# 03_-_VOLTAGE_REGULATION.net
KiCad netlist of a schematic drawn in Altium Designer
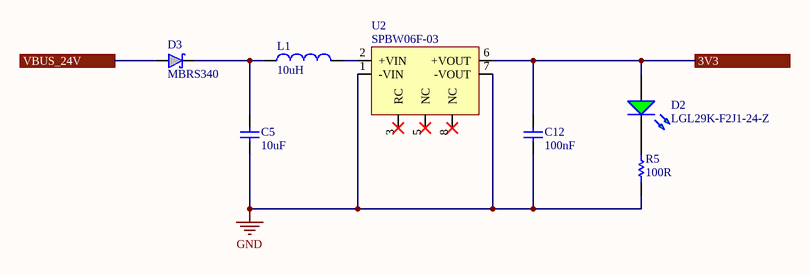
[diagram p0: [03] - VOLTAGE REGULATION.SchDoc]

(export (version "E")
  (design (tool "Eeschema 10.0.6"))
  (components
    (comp (ref "C5")
      (value "10uF")
      (footprint "INCH 1206 - METRIC 3216 - H180")
      (description "CAP CER 10UF 50V X5R 1206")
      (fields
        (field (name "MANUFACTURER") "TDK")
        (field (name "MANUFACTURER PART NUMBER") "C3216X5R1H106K160AB")
      )
      (libsource (lib "Capacitors") (part "C3216X5R1H106K160AB"))
    )
    (comp (ref "C12")
      (value "100nF")
      (footprint "INCH 0603 - METRIC 1608 - H090")
      (description "CAP CER 0.1UF 25V X7R 0603")
      (fields
        (field (name "MANUFACTURER") "TDK")
        (field (name "MANUFACTURER PART NUMBER") "CGA3E2X7R1E104K080AA")
      )
      (libsource (lib "Capacitors") (part "CGA3E2X7R1E104K080AA"))
    )
    (comp (ref "D2")
      (value "LGL29K-F2J1-24-Z")
      (footprint "LED - 0603 - GREEN")
      (description "LED GREEN DIFFUSED 0603 SMD")
      (fields (field (name "MANUFACTURER") "Osram Opto"))
      (libsource (lib "LEDs") (part "LGL29K-F2J1-24-Z"))
    )
    (comp (ref "D3")
      (value "MBRS340")
      (footprint "D0-214AB SMC - L")
      (description "DIODE SCHOTTKY 40V 4A SMC")
      (fields (field (name "MANUFACTURER") "ON Semiconductor / Fairchild"))
      (libsource (lib "Diodes") (part "MBRS340"))
    )
    (comp (ref "L1")
      (value "10uH")
      (footprint "VISHAY_IHLP2020BZER100M01")
      (description "FIXED IND 10UH 2.3A 199 MOHM SMD")
      (fields
        (field (name "MANUFACTURER") "Vishay Dale")
        (field (name "MANUFACTURER PART NUMBER") "IHLP2020BZER100M01")
      )
      (libsource (lib "Inductors") (part "IHLP2020BZER100M01"))
    )
    (comp (ref "R5")
      (value "100R")
      (footprint "INCH 0603 - METRIC 1608 - H055")
      (description "RES SMD 100 OHM 0.1% 1/16W 0603")
      (fields
        (field (name "MANUFACTURER") "TE Connectivity Neohm")
        (field (name "MANUFACTURER PART NUMBER") "CPF0603B100RE1")
      )
      (libsource (lib "Resistors") (part "CPF0603B100RE1"))
    )
    (comp (ref "U2")
      (value "SPBW06F-03")
      (footprint "SPBW06F-03")
      (description "DC DC CONVERTER 3.3V 5W")
      (fields (field (name "MANUFACTURER") "Mean Well"))
      (libsource (lib "Voltage Regulators - Switching") (part "SPBW06F-03"))
    )
  )
  (nets
    (net (code "1") (name "/3V3") (class "Default")
      (node (ref "C12") (pin "2") (pintype "passive"))
      (node (ref "D2") (pin "A") (pintype "passive"))
      (node (ref "U2") (pin "6") (pinfunction "+VOUT_6") (pintype "passive"))
    )
    (net (code "2") (name "/VBUS_24V") (class "Default") (node (ref "D3") (pin "2") (pintype "passive")))
    (net (code "3") (name "GND") (class "Default")
      (node (ref "C12") (pin "1") (pintype "passive"))
      (node (ref "C5") (pin "1") (pintype "passive"))
      (node (ref "R5") (pin "2") (pintype "passive"))
      (node (ref "U2") (pin "1") (pinfunction "-VIN_1") (pintype "passive"))
      (node (ref "U2") (pin "7") (pinfunction "-VOUT_7") (pintype "passive"))
    )
    (net (code "4") (name "Net-(C5-Pad2)") (class "Default")
      (node (ref "C5") (pin "2") (pintype "passive"))
      (node (ref "D3") (pin "1") (pintype "passive"))
      (node (ref "L1") (pin "1") (pinfunction "1_1") (pintype "passive"))
    )
    (net (code "5") (name "Net-(D2-PadC)") (class "Default")
      (node (ref "D2") (pin "C") (pintype "passive"))
      (node (ref "R5") (pin "1") (pintype "passive"))
    )
    (net (code "6") (name "Net-(U2-+VIN)") (class "Default")
      (node (ref "L1") (pin "2") (pinfunction "2_2") (pintype "passive"))
      (node (ref "U2") (pin "2") (pinfunction "+VIN_2") (pintype "passive"))
    )
    (net (code "7") (name "unconnected-(U2-NC-Pad5)") (class "Default")
      (node (ref "U2") (pin "5") (pinfunction "NC_5") (pintype "passive+no_connect"))
    )
    (net (code "8") (name "unconnected-(U2-NC-Pad8)") (class "Default")
      (node (ref "U2") (pin "8") (pinfunction "NC_8") (pintype "passive+no_connect"))
    )
    (net (code "9") (name "unconnected-(U2-RC-Pad3)") (class "Default")
      (node (ref "U2") (pin "3") (pinfunction "RC_3") (pintype "passive+no_connect"))
    )
  )
)
